# BT832A.net
KiCad netlist of a schematic drawn in EAGLE
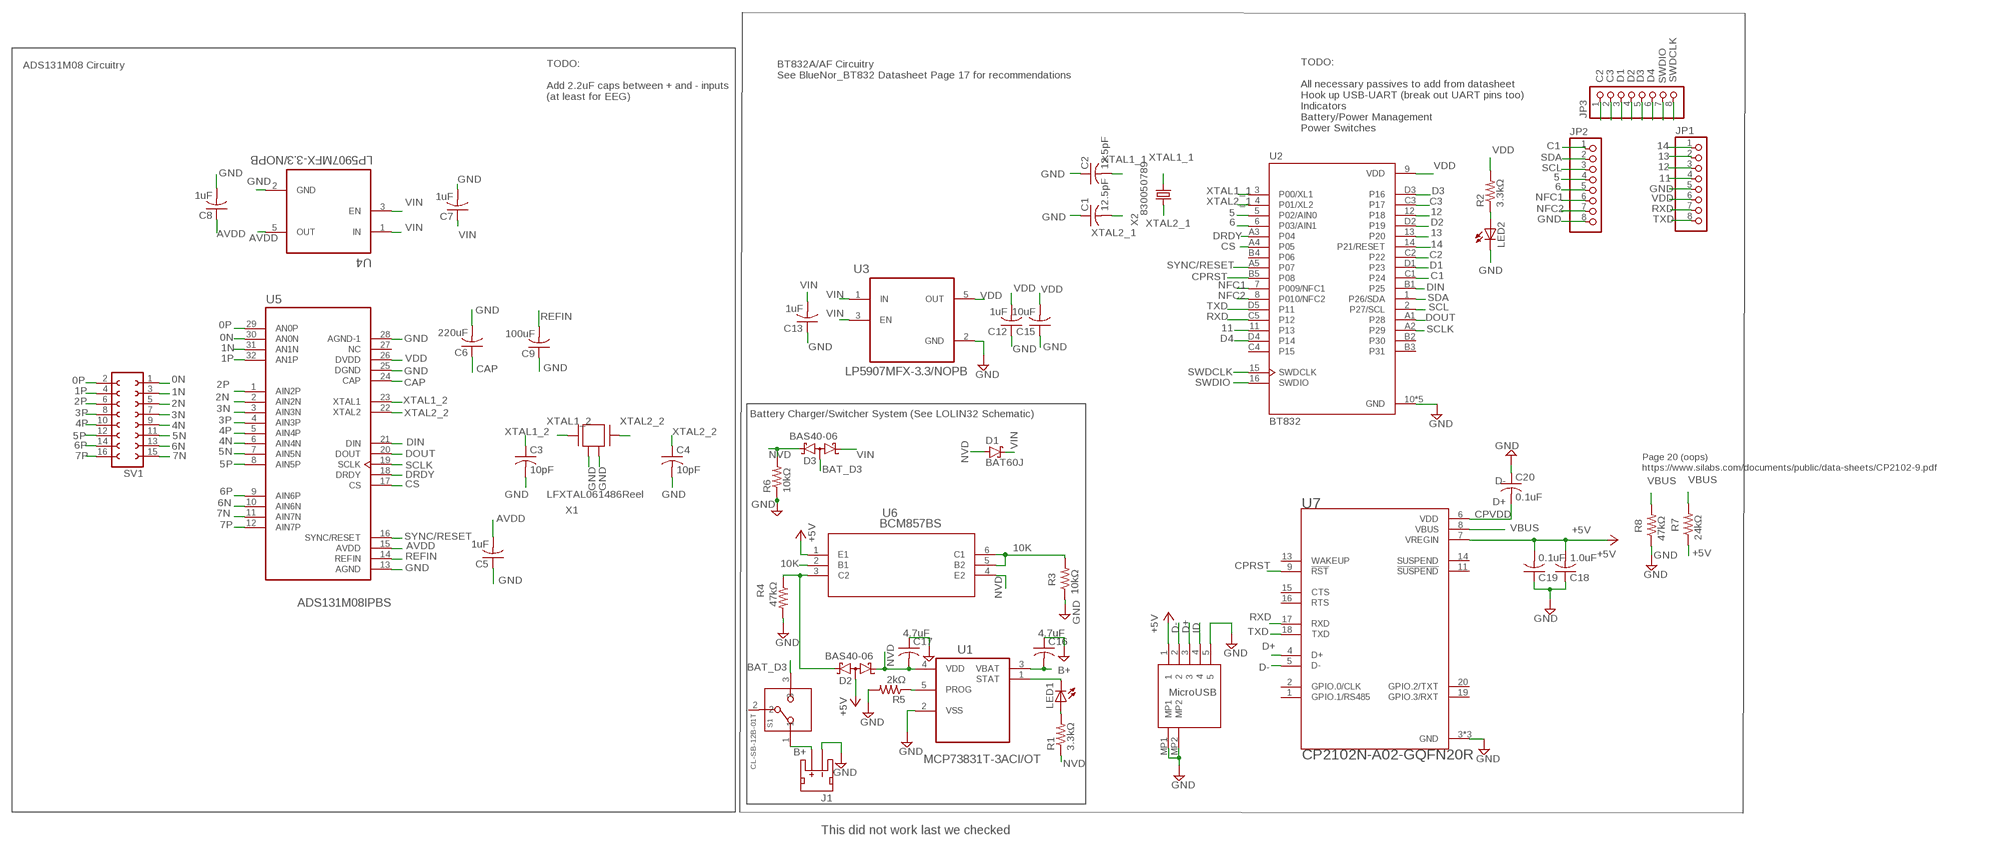
[diagram p0: schematic, sheet 1]

(export (version "E")
  (design (tool "Eeschema 10.0.6"))
  (components
    (comp (ref "C1")
      (value "12.5pF")
      (footprint "eagle-import:C0402")
      (libsource (lib "eagle-import") (part "adafruit_420_C-USC0402"))
    )
    (comp (ref "C2")
      (value "12.5pF")
      (footprint "eagle-import:C0402")
      (libsource (lib "eagle-import") (part "adafruit_420_C-USC0402"))
    )
    (comp (ref "C3")
      (value "10pF")
      (footprint "eagle-import:C0402")
      (libsource (lib "eagle-import") (part "adafruit_420_C-USC0402"))
    )
    (comp (ref "C4")
      (value "10pF")
      (footprint "eagle-import:C0402")
      (libsource (lib "eagle-import") (part "adafruit_420_C-USC0402"))
    )
    (comp (ref "C5")
      (value "1uF")
      (footprint "eagle-import:C0402")
      (libsource (lib "eagle-import") (part "C-USC0402"))
    )
    (comp (ref "C6")
      (value "220uF")
      (footprint "eagle-import:C0402")
      (libsource (lib "eagle-import") (part "C-USC0402"))
    )
    (comp (ref "C7")
      (value "1uF")
      (footprint "eagle-import:C0402")
      (libsource (lib "eagle-import") (part "C-USC0402"))
    )
    (comp (ref "C8")
      (value "1uF")
      (footprint "eagle-import:C0402")
      (libsource (lib "eagle-import") (part "C-USC0402"))
    )
    (comp (ref "C9")
      (value "100uF")
      (footprint "eagle-import:C0402")
      (libsource (lib "eagle-import") (part "C-USC0402"))
    )
    (comp (ref "C12")
      (value "1uF")
      (footprint "eagle-import:C0402")
      (libsource (lib "eagle-import") (part "C-USC0402"))
    )
    (comp (ref "C13")
      (value "1uF")
      (footprint "eagle-import:C0402")
      (libsource (lib "eagle-import") (part "C-USC0402"))
    )
    (comp (ref "C15")
      (value "10uF")
      (footprint "eagle-import:C0402")
      (libsource (lib "eagle-import") (part "C-USC0402"))
    )
    (comp (ref "C16")
      (value "4.7uF")
      (footprint "eagle-import:C0402")
      (libsource (lib "eagle-import") (part "adafruit_420_C-USC0402"))
    )
    (comp (ref "C17")
      (value "4.7uF")
      (footprint "eagle-import:C0402")
      (libsource (lib "eagle-import") (part "adafruit_420_C-USC0402"))
    )
    (comp (ref "C18")
      (value "1.0uF")
      (footprint "eagle-import:C0402")
      (libsource (lib "eagle-import") (part "adafruit_420_C-USC0402"))
    )
    (comp (ref "C19")
      (value "0.1uF")
      (footprint "eagle-import:C0402")
      (libsource (lib "eagle-import") (part "adafruit_420_C-USC0402"))
    )
    (comp (ref "C20")
      (value "0.1uF")
      (footprint "eagle-import:C0402")
      (libsource (lib "eagle-import") (part "adafruit_420_C-USC0402"))
    )
    (comp (ref "D1")
      (value "BAT60J")
      (footprint "eagle-import:SOD323_ST")
      (libsource (lib "eagle-import") (part "BAT60J"))
    )
    (comp (ref "D2")
      (value "BAS40-06")
      (footprint "eagle-import:SOT23")
      (libsource (lib "eagle-import") (part "BAS40-06"))
    )
    (comp (ref "D3")
      (value "BAS40-06")
      (footprint "eagle-import:SOT23")
      (libsource (lib "eagle-import") (part "BAS40-06"))
    )
    (comp (ref "J1")
      (value "JST_2MM_MALE")
      (footprint "eagle-import:JST-2-SMD")
      (libsource (lib "eagle-import") (part "JST_2MM_MALE"))
    )
    (comp (ref "JP1")
      (value "PINHD-1X8CLEANBIG")
      (footprint "eagle-import:1X08-CLEANBIG")
      (libsource (lib "eagle-import") (part "PINHD-1X8CLEANBIG"))
    )
    (comp (ref "JP2")
      (value "PINHD-1X8CLEANBIG")
      (footprint "eagle-import:1X08-CLEANBIG")
      (libsource (lib "eagle-import") (part "PINHD-1X8CLEANBIG"))
    )
    (comp (ref "JP3")
      (value "PINHD-1X8CLEANBIG")
      (footprint "eagle-import:1X08-CLEANBIG")
      (libsource (lib "eagle-import") (part "PINHD-1X8CLEANBIG"))
    )
    (comp (ref "LED1")
      (value "LEDCHIP-LED0603")
      (footprint "eagle-import:CHIP-LED0603")
      (libsource (lib "eagle-import") (part "LEDCHIP-LED0603"))
    )
    (comp (ref "LED2")
      (value "LEDCHIP-LED0603")
      (footprint "eagle-import:CHIP-LED0603")
      (libsource (lib "eagle-import") (part "LEDCHIP-LED0603"))
    )
    (comp (ref "R1")
      (value "3.3kΩ")
      (footprint "eagle-import:R0402")
      (libsource (lib "eagle-import") (part "R-US_R0402"))
    )
    (comp (ref "R2")
      (value "3.3kΩ")
      (footprint "eagle-import:R0402")
      (libsource (lib "eagle-import") (part "R-US_R0402"))
    )
    (comp (ref "R3")
      (value "10kΩ")
      (footprint "eagle-import:R0402")
      (libsource (lib "eagle-import") (part "R-US_R0402"))
    )
    (comp (ref "R4")
      (value "47kΩ")
      (footprint "eagle-import:R0402")
      (libsource (lib "eagle-import") (part "R-US_R0402"))
    )
    (comp (ref "R5")
      (value "2kΩ")
      (footprint "eagle-import:R0402")
      (libsource (lib "eagle-import") (part "R-US_R0402"))
    )
    (comp (ref "R6")
      (value "10kΩ")
      (footprint "eagle-import:R0402")
      (libsource (lib "eagle-import") (part "R-US_R0402"))
    )
    (comp (ref "R7")
      (value "24kΩ")
      (footprint "eagle-import:R0402")
      (libsource (lib "eagle-import") (part "R-US_R0402"))
    )
    (comp (ref "R8")
      (value "47kΩ")
      (footprint "eagle-import:R0402")
      (libsource (lib "eagle-import") (part "R-US_R0402"))
    )
    (comp (ref "S1")
      (value "CL-SB-12B-01T")
      (footprint "eagle-import:CL-SB-12B")
      (fields (field (name "MF") "Nidec Copal"))
      (libsource (lib "eagle-import") (part "CL-SB-12B-01T"))
    )
    (comp (ref "SV1")
      (value "FE08-2")
      (footprint "eagle-import:FE08-2")
      (libsource (lib "eagle-import") (part "FE08-2"))
    )
    (comp (ref "U$1")
      (value "DX4R005JJ2R1800")
      (footprint "eagle-import:DX4R005JJ2R1800")
      (fields (field (name "MF") "JAE Electronics"))
      (libsource (lib "eagle-import") (part "DX4R005JJ2R1800"))
    )
    (comp (ref "U1")
      (value "MCP73831T-3ACI/OT")
      (footprint "eagle-import:SOT95P270X145-5N")
      (fields (field (name "MF") "Microchip"))
      (libsource (lib "eagle-import") (part "MCP73831T-3ACI/OT"))
    )
    (comp (ref "U2")
      (value "BT832")
      (footprint "eagle-import:BLEMODULE_BT832")
      (fields (field (name "MF") "Fanstel Corp."))
      (libsource (lib "eagle-import") (part "BT832"))
    )
    (comp (ref "U3")
      (value "LP5907MFX-3.3/NOPB")
      (footprint "eagle-import:SOT95P280X145-5N")
      (fields (field (name "MF") "Texas Instruments"))
      (libsource (lib "eagle-import") (part "LP5907MFX-3.3/NOPB"))
    )
    (comp (ref "U4")
      (value "LP5907MFX-3.3/NOPB")
      (footprint "eagle-import:SOT95P280X145-5N")
      (fields (field (name "MF") "Texas Instruments"))
      (libsource (lib "eagle-import") (part "LP5907MFX-3.3/NOPB"))
    )
    (comp (ref "U5")
      (value "ADS131M08IPBS")
      (footprint "eagle-import:QFP50P700X700X120-32N")
      (fields (field (name "MF") "Texas Instruments"))
      (libsource (lib "eagle-import") (part "ADS131M08IPBS"))
    )
    (comp (ref "U6")
      (value "BCM857BS")
      (footprint "eagle-import:SOT363_NEX")
      (fields (field (name "COPYRIGHT") "Copyright (C) 2016 Accelerated Designs. All rights reserved"))
      (libsource (lib "eagle-import") (part "BCM857BS"))
    )
    (comp (ref "U7")
      (value "CP2102N-A02-GQFN20R")
      (footprint "eagle-import:SILABS_CP2102N-A02-GQFN20R")
      (fields (field (name "MF") "Silicon Labs"))
      (libsource (lib "eagle-import") (part "CP2102N-A02-GQFN20R"))
    )
    (comp (ref "X1")
      (value "ABM3B-8.000MHZ-B2-T")
      (footprint "eagle-import:ABM3B-8.000MHZ-B2-T")
      (fields
        (field (name "DIGIKEY_PART_NUMBER") "535-9720-2-ND")
        (field (name "MANUFACTURER") "Abracon LLC")
        (field (name "CREATED_BY") "PCBLayout.com")
      )
      (libsource (lib "eagle-import") (part "ABM3B-8.000MHZ-B2-T"))
    )
    (comp (ref "X2")
      (value "FC-12M")
      (footprint "eagle-import:FC-12M")
      (libsource (lib "eagle-import") (part "FC-12M"))
    )
  )
  (nets
    (net (code "1") (name "+5V") (class "Default")
      (node (ref "C18") (pin "2") (pinfunction "2_2") (pintype "passive"))
      (node (ref "C19") (pin "2") (pinfunction "2_2") (pintype "passive"))
      (node (ref "D2") (pin "3") (pinfunction "AA_3") (pintype "passive"))
      (node (ref "R7") (pin "1") (pinfunction "1_1") (pintype "passive"))
      (node (ref "U$1") (pin "1") (pinfunction "1_1") (pintype "bidirectional"))
      (node (ref "U6") (pin "1") (pinfunction "E1_1") (pintype "passive"))
      (node (ref "U7") (pin "7") (pinfunction "VREGIN_7") (pintype "power_in"))
    )
    (net (code "2") (name "0N") (class "Default")
      (node (ref "SV1") (pin "1") (pinfunction "1_1") (pintype "passive"))
      (node (ref "U5") (pin "30") (pinfunction "AN0N_30") (pintype "bidirectional"))
    )
    (net (code "3") (name "0P") (class "Default")
      (node (ref "SV1") (pin "2") (pinfunction "2_2") (pintype "passive"))
      (node (ref "U5") (pin "29") (pinfunction "AN0P_29") (pintype "bidirectional"))
    )
    (net (code "4") (name "1N") (class "Default")
      (node (ref "SV1") (pin "3") (pinfunction "3_3") (pintype "passive"))
      (node (ref "U5") (pin "31") (pinfunction "AN1N_31") (pintype "bidirectional"))
    )
    (net (code "5") (name "1P") (class "Default")
      (node (ref "SV1") (pin "4") (pinfunction "4_4") (pintype "passive"))
      (node (ref "U5") (pin "32") (pinfunction "AN1P_32") (pintype "bidirectional"))
    )
    (net (code "6") (name "2N") (class "Default")
      (node (ref "SV1") (pin "5") (pinfunction "5_5") (pintype "passive"))
      (node (ref "U5") (pin "2") (pinfunction "AIN2N_2") (pintype "input"))
    )
    (net (code "7") (name "2P") (class "Default")
      (node (ref "SV1") (pin "6") (pinfunction "6_6") (pintype "passive"))
      (node (ref "U5") (pin "1") (pinfunction "AIN2P_1") (pintype "input"))
    )
    (net (code "8") (name "3N") (class "Default")
      (node (ref "SV1") (pin "7") (pinfunction "7_7") (pintype "passive"))
      (node (ref "U5") (pin "3") (pinfunction "AIN3N_3") (pintype "input"))
    )
    (net (code "9") (name "3P") (class "Default")
      (node (ref "SV1") (pin "8") (pinfunction "8_8") (pintype "passive"))
      (node (ref "U5") (pin "4") (pinfunction "AIN3P_4") (pintype "input"))
    )
    (net (code "10") (name "4N") (class "Default")
      (node (ref "SV1") (pin "9") (pinfunction "9_9") (pintype "passive"))
      (node (ref "U5") (pin "6") (pinfunction "AIN4N_6") (pintype "input"))
    )
    (net (code "11") (name "4P") (class "Default")
      (node (ref "SV1") (pin "10") (pinfunction "10_10") (pintype "passive"))
      (node (ref "U5") (pin "5") (pinfunction "AIN4P_5") (pintype "input"))
    )
    (net (code "12") (name "5") (class "Default")
      (node (ref "JP2") (pin "4") (pinfunction "4_4") (pintype "passive"))
      (node (ref "U2") (pin "5") (pinfunction "P02/AIN0_5") (pintype "bidirectional"))
    )
    (net (code "13") (name "5N") (class "Default")
      (node (ref "SV1") (pin "11") (pinfunction "11_11") (pintype "passive"))
      (node (ref "U5") (pin "7") (pinfunction "AIN5N_7") (pintype "input"))
    )
    (net (code "14") (name "5P") (class "Default")
      (node (ref "SV1") (pin "12") (pinfunction "12_12") (pintype "passive"))
      (node (ref "U5") (pin "8") (pinfunction "AIN5P_8") (pintype "input"))
    )
    (net (code "15") (name "6") (class "Default")
      (node (ref "JP2") (pin "5") (pinfunction "5_5") (pintype "passive"))
      (node (ref "U2") (pin "6") (pinfunction "P03/AIN1_6") (pintype "bidirectional"))
    )
    (net (code "16") (name "6N") (class "Default")
      (node (ref "SV1") (pin "13") (pinfunction "13_13") (pintype "passive"))
      (node (ref "U5") (pin "10") (pinfunction "AIN6N_10") (pintype "input"))
    )
    (net (code "17") (name "6P") (class "Default")
      (node (ref "SV1") (pin "14") (pinfunction "14_14") (pintype "passive"))
      (node (ref "U5") (pin "9") (pinfunction "AIN6P_9") (pintype "input"))
    )
    (net (code "18") (name "7N") (class "Default")
      (node (ref "SV1") (pin "15") (pinfunction "15_15") (pintype "passive"))
      (node (ref "U5") (pin "11") (pinfunction "AIN7N_11") (pintype "input"))
    )
    (net (code "19") (name "7P") (class "Default")
      (node (ref "SV1") (pin "16") (pinfunction "16_16") (pintype "passive"))
      (node (ref "U5") (pin "12") (pinfunction "AIN7P_12") (pintype "input"))
    )
    (net (code "20") (name "10K") (class "Default")
      (node (ref "R3") (pin "2") (pinfunction "2_2") (pintype "passive"))
      (node (ref "U6") (pin "2") (pinfunction "B1_2") (pintype "passive"))
      (node (ref "U6") (pin "5") (pinfunction "B2_5") (pintype "passive"))
      (node (ref "U6") (pin "6") (pinfunction "C1_6") (pintype "passive"))
    )
    (net (code "21") (name "11") (class "Default")
      (node (ref "JP1") (pin "4") (pinfunction "4_4") (pintype "passive"))
      (node (ref "U2") (pin "11") (pinfunction "P13_11") (pintype "bidirectional"))
    )
    (net (code "22") (name "12") (class "Default")
      (node (ref "JP1") (pin "3") (pinfunction "3_3") (pintype "passive"))
      (node (ref "U2") (pin "12") (pinfunction "P18_12") (pintype "bidirectional"))
    )
    (net (code "23") (name "13") (class "Default")
      (node (ref "JP1") (pin "2") (pinfunction "2_2") (pintype "passive"))
      (node (ref "U2") (pin "13") (pinfunction "P20_13") (pintype "bidirectional"))
    )
    (net (code "24") (name "14") (class "Default")
      (node (ref "JP1") (pin "1") (pinfunction "1_1") (pintype "passive"))
      (node (ref "U2") (pin "14") (pinfunction "P21/RESET_14") (pintype "bidirectional"))
    )
    (net (code "25") (name "AVDD") (class "Default")
      (node (ref "C5") (pin "2") (pinfunction "2_2") (pintype "passive"))
      (node (ref "C8") (pin "1") (pinfunction "1_1") (pintype "passive"))
      (node (ref "U4") (pin "5") (pinfunction "OUT_5") (pintype "output"))
      (node (ref "U5") (pin "15") (pinfunction "AVDD_15") (pintype "power_in"))
    )
    (net (code "26") (name "B+") (class "Default")
      (node (ref "C16") (pin "2") (pinfunction "2_2") (pintype "passive"))
      (node (ref "J1") (pin "2") (pinfunction "+_2") (pintype "bidirectional"))
      (node (ref "S1") (pin "1") (pinfunction "1_1") (pintype "bidirectional"))
      (node (ref "U1") (pin "3") (pinfunction "VBAT_3") (pintype "power_in"))
    )
    (net (code "27") (name "BAT_D3") (class "Default")
      (node (ref "D3") (pin "3") (pinfunction "AA_3") (pintype "passive"))
      (node (ref "S1") (pin "3") (pinfunction "3_3") (pintype "bidirectional"))
    )
    (net (code "28") (name "C1") (class "Default")
      (node (ref "JP2") (pin "1") (pinfunction "1_1") (pintype "passive"))
      (node (ref "U2") (pin "C1") (pinfunction "P24_C1") (pintype "bidirectional"))
    )
    (net (code "29") (name "C2") (class "Default")
      (node (ref "JP3") (pin "1") (pinfunction "1_1") (pintype "passive"))
      (node (ref "U2") (pin "C2") (pinfunction "P22_C2") (pintype "bidirectional"))
    )
    (net (code "30") (name "C3") (class "Default")
      (node (ref "JP3") (pin "2") (pinfunction "2_2") (pintype "passive"))
      (node (ref "U2") (pin "C3") (pinfunction "P17_C3") (pintype "bidirectional"))
    )
    (net (code "31") (name "CAP") (class "Default")
      (node (ref "C6") (pin "1") (pinfunction "1_1") (pintype "passive"))
      (node (ref "U5") (pin "24") (pinfunction "CAP_24") (pintype "bidirectional"))
    )
    (net (code "32") (name "CPRST") (class "Default")
      (node (ref "U2") (pin "B5") (pinfunction "P08_B5") (pintype "bidirectional"))
      (node (ref "U7") (pin "9") (pinfunction "~{RST}_9") (pintype "input"))
    )
    (net (code "33") (name "CPVDD") (class "Default")
      (node (ref "C20") (pin "2") (pinfunction "2_2") (pintype "passive"))
      (node (ref "U7") (pin "6") (pinfunction "VDD_6") (pintype "power_in"))
    )
    (net (code "34") (name "CS") (class "Default")
      (node (ref "U2") (pin "A4") (pinfunction "P05_A4") (pintype "bidirectional"))
      (node (ref "U5") (pin "17") (pinfunction "CS_17") (pintype "bidirectional"))
    )
    (net (code "35") (name "D+") (class "Default")
      (node (ref "U$1") (pin "3") (pinfunction "3_3") (pintype "bidirectional"))
      (node (ref "U7") (pin "4") (pinfunction "D+_4") (pintype "bidirectional"))
    )
    (net (code "36") (name "D-") (class "Default")
      (node (ref "U$1") (pin "2") (pinfunction "2_2") (pintype "bidirectional"))
      (node (ref "U7") (pin "5") (pinfunction "D-_5") (pintype "bidirectional"))
    )
    (net (code "37") (name "D1") (class "Default")
      (node (ref "JP3") (pin "3") (pinfunction "3_3") (pintype "passive"))
      (node (ref "U2") (pin "D1") (pinfunction "P23_D1") (pintype "bidirectional"))
    )
    (net (code "38") (name "D2") (class "Default")
      (node (ref "JP3") (pin "4") (pinfunction "4_4") (pintype "passive"))
      (node (ref "U2") (pin "D2") (pinfunction "P19_D2") (pintype "bidirectional"))
    )
    (net (code "39") (name "D3") (class "Default")
      (node (ref "JP3") (pin "5") (pinfunction "5_5") (pintype "passive"))
      (node (ref "U2") (pin "D3") (pinfunction "P16_D3") (pintype "bidirectional"))
    )
    (net (code "40") (name "D4") (class "Default")
      (node (ref "JP3") (pin "6") (pinfunction "6_6") (pintype "passive"))
      (node (ref "U2") (pin "D4") (pinfunction "P14_D4") (pintype "bidirectional"))
    )
    (net (code "41") (name "DIN") (class "Default")
      (node (ref "U2") (pin "B1") (pinfunction "P25_B1") (pintype "bidirectional"))
      (node (ref "U5") (pin "21") (pinfunction "DIN_21") (pintype "input"))
    )
    (net (code "42") (name "DOUT") (class "Default")
      (node (ref "U2") (pin "A1") (pinfunction "P28_A1") (pintype "bidirectional"))
      (node (ref "U5") (pin "20") (pinfunction "DOUT_20") (pintype "output"))
    )
    (net (code "43") (name "DRDY") (class "Default")
      (node (ref "U2") (pin "A3") (pinfunction "P04_A3") (pintype "bidirectional"))
      (node (ref "U5") (pin "18") (pinfunction "DRDY_18") (pintype "output"))
    )
    (net (code "44") (name "GND") (class "Default")
      (node (ref "C1") (pin "1") (pinfunction "1_1") (pintype "passive"))
      (node (ref "C12") (pin "1") (pinfunction "1_1") (pintype "passive"))
      (node (ref "C13") (pin "1") (pinfunction "1_1") (pintype "passive"))
      (node (ref "C15") (pin "1") (pinfunction "1_1") (pintype "passive"))
      (node (ref "C16") (pin "1") (pinfunction "1_1") (pintype "passive"))
      (node (ref "C17") (pin "1") (pinfunction "1_1") (pintype "passive"))
      (node (ref "C18") (pin "1") (pinfunction "1_1") (pintype "passive"))
      (node (ref "C19") (pin "1") (pinfunction "1_1") (pintype "passive"))
      (node (ref "C2") (pin "1") (pinfunction "1_1") (pintype "passive"))
      (node (ref "C20") (pin "1") (pinfunction "1_1") (pintype "passive"))
      (node (ref "C3") (pin "2") (pinfunction "2_2") (pintype "passive"))
      (node (ref "C4") (pin "2") (pinfunction "2_2") (pintype "passive"))
      (node (ref "C5") (pin "1") (pinfunction "1_1") (pintype "passive"))
      (node (ref "C6") (pin "2") (pinfunction "2_2") (pintype "passive"))
      (node (ref "C7") (pin "2") (pinfunction "2_2") (pintype "passive"))
      (node (ref "C8") (pin "2") (pinfunction "2_2") (pintype "passive"))
      (node (ref "C9") (pin "1") (pinfunction "1_1") (pintype "passive"))
      (node (ref "J1") (pin "1") (pinfunction "-_1") (pintype "bidirectional"))
      (node (ref "JP1") (pin "5") (pinfunction "5_5") (pintype "passive"))
      (node (ref "JP2") (pin "8") (pinfunction "8_8") (pintype "passive"))
      (node (ref "LED2") (pin "C") (pinfunction "C_C") (pintype "passive"))
      (node (ref "R3") (pin "1") (pinfunction "1_1") (pintype "passive"))
      (node (ref "R4") (pin "2") (pinfunction "2_2") (pintype "passive"))
      (node (ref "R5") (pin "2") (pinfunction "2_2") (pintype "passive"))
      (node (ref "R6") (pin "1") (pinfunction "1_1") (pintype "passive"))
      (node (ref "R8") (pin "1") (pinfunction "1_1") (pintype "passive"))
      (node (ref "U$1") (pin "5") (pinfunction "5_5") (pintype "bidirectional"))
      (node (ref "U$1") (pin "MP1") (pinfunction "MP1_MP1") (pintype "bidirectional"))
      (node (ref "U$1") (pin "MP2") (pinfunction "MP2_MP2") (pintype "bidirectional"))
      (node (ref "U1") (pin "2") (pinfunction "VSS_2") (pintype "power_in"))
      (node (ref "U2") (pin "10") (pinfunction "GND_10") (pintype "power_in"))
      (node (ref "U2") (pin "A0") (pinfunction "GND_A0") (pintype "power_in"))
      (node (ref "U2") (pin "B0") (pinfunction "GND_B0") (pintype "power_in"))
      (node (ref "U2") (pin "C0") (pinfunction "GND_C0") (pintype "power_in"))
      (node (ref "U2") (pin "D0") (pinfunction "GND_D0") (pintype "power_in"))
      (node (ref "U3") (pin "2") (pinfunction "GND_2") (pintype "power_in"))
      (node (ref "U4") (pin "2") (pinfunction "GND_2") (pintype "power_in"))
      (node (ref "U5") (pin "13") (pinfunction "AGND_13") (pintype "power_in"))
      (node (ref "U5") (pin "25") (pinfunction "DGND_25") (pintype "power_in"))
      (node (ref "U5") (pin "28") (pinfunction "AGND-1_28") (pintype "power_in"))
      (node (ref "U7") (pin "12") (pinfunction "GND_12") (pintype "power_in"))
      (node (ref "U7") (pin "21") (pinfunction "GND_21") (pintype "power_in"))
      (node (ref "U7") (pin "3") (pinfunction "GND_3") (pintype "power_in"))
      (node (ref "X1") (pin "2") (pinfunction "2_2") (pintype "passive"))
      (node (ref "X1") (pin "4") (pinfunction "4_4") (pintype "passive"))
    )
    (net (code "45") (name "ID") (class "Default")
      (node (ref "U$1") (pin "4") (pinfunction "4_4") (pintype "bidirectional"))
    )
    (net (code "46") (name "NFC1") (class "Default")
      (node (ref "JP2") (pin "6") (pinfunction "6_6") (pintype "passive"))
      (node (ref "U2") (pin "7") (pinfunction "P009/NFC1_7") (pintype "bidirectional"))
    )
    (net (code "47") (name "NFC2") (class "Default")
      (node (ref "JP2") (pin "7") (pinfunction "7_7") (pintype "passive"))
      (node (ref "U2") (pin "8") (pinfunction "P010/NFC2_8") (pintype "bidirectional"))
    )
    (net (code "48") (name "NVD") (class "Default")
      (node (ref "C17") (pin "2") (pinfunction "2_2") (pintype "passive"))
      (node (ref "D1") (pin "A") (pinfunction "A_A") (pintype "passive"))
      (node (ref "D2") (pin "1") (pinfunction "K1_1") (pintype "passive"))
      (node (ref "D3") (pin "2") (pinfunction "K2_2") (pintype "passive"))
      (node (ref "R1") (pin "1") (pinfunction "1_1") (pintype "passive"))
      (node (ref "R6") (pin "2") (pinfunction "2_2") (pintype "passive"))
      (node (ref "U1") (pin "4") (pinfunction "VDD_4") (pintype "power_in"))
      (node (ref "U6") (pin "4") (pinfunction "E2_4") (pintype "passive"))
    )
    (net (code "49") (name "Net-(D2-K2)") (class "Default")
      (node (ref "D2") (pin "2") (pinfunction "K2_2") (pintype "passive"))
      (node (ref "R4") (pin "1") (pinfunction "1_1") (pintype "passive"))
      (node (ref "U6") (pin "3") (pinfunction "C2_3") (pintype "passive"))
    )
    (net (code "50") (name "Net-(LED1-PadA)") (class "Default")
      (node (ref "LED1") (pin "A") (pinfunction "A_A") (pintype "passive"))
      (node (ref "R1") (pin "2") (pinfunction "2_2") (pintype "passive"))
    )
    (net (code "51") (name "Net-(LED2-PadA)") (class "Default")
      (node (ref "LED2") (pin "A") (pinfunction "A_A") (pintype "passive"))
      (node (ref "R2") (pin "1") (pinfunction "1_1") (pintype "passive"))
    )
    (net (code "52") (name "Net-(U1-PROG)") (class "Default")
      (node (ref "R5") (pin "1") (pinfunction "1_1") (pintype "passive"))
      (node (ref "U1") (pin "5") (pinfunction "PROG_5") (pintype "input"))
    )
    (net (code "53") (name "Net-(U1-STAT)") (class "Default")
      (node (ref "LED1") (pin "C") (pinfunction "C_C") (pintype "passive"))
      (node (ref "U1") (pin "1") (pinfunction "STAT_1") (pintype "output"))
    )
    (net (code "54") (name "REFIN") (class "Default")
      (node (ref "C9") (pin "2") (pinfunction "2_2") (pintype "passive"))
      (node (ref "U5") (pin "14") (pinfunction "REFIN_14") (pintype "input"))
    )
    (net (code "55") (name "RXD") (class "Default")
      (node (ref "JP1") (pin "7") (pinfunction "7_7") (pintype "passive"))
      (node (ref "U2") (pin "C5") (pinfunction "P12_C5") (pintype "bidirectional"))
      (node (ref "U7") (pin "17") (pinfunction "RXD_17") (pintype "input"))
    )
    (net (code "56") (name "SCL") (class "Default")
      (node (ref "JP2") (pin "3") (pinfunction "3_3") (pintype "passive"))
      (node (ref "U2") (pin "2") (pinfunction "P27/SCL_2") (pintype "bidirectional"))
    )
    (net (code "57") (name "SCLK") (class "Default")
      (node (ref "U2") (pin "A2") (pinfunction "P29_A2") (pintype "bidirectional"))
      (node (ref "U5") (pin "19") (pinfunction "SCLK_19") (pintype "input"))
    )
    (net (code "58") (name "SDA") (class "Default")
      (node (ref "JP2") (pin "2") (pinfunction "2_2") (pintype "passive"))
      (node (ref "U2") (pin "1") (pinfunction "P26/SDA_1") (pintype "bidirectional"))
    )
    (net (code "59") (name "SWDCLK") (class "Default")
      (node (ref "JP3") (pin "8") (pinfunction "8_8") (pintype "passive"))
      (node (ref "U2") (pin "15") (pinfunction "SWDCLK_15") (pintype "input"))
    )
    (net (code "60") (name "SWDIO") (class "Default")
      (node (ref "JP3") (pin "7") (pinfunction "7_7") (pintype "passive"))
      (node (ref "U2") (pin "16") (pinfunction "SWDIO_16") (pintype "bidirectional"))
    )
    (net (code "61") (name "SYNC{slash}RESET") (class "Default")
      (node (ref "U2") (pin "A5") (pinfunction "P07_A5") (pintype "bidirectional"))
      (node (ref "U5") (pin "16") (pinfunction "SYNC/RESET_16") (pintype "bidirectional"))
    )
    (net (code "62") (name "TXD") (class "Default")
      (node (ref "JP1") (pin "8") (pinfunction "8_8") (pintype "passive"))
      (node (ref "U2") (pin "D5") (pinfunction "P11_D5") (pintype "bidirectional"))
      (node (ref "U7") (pin "18") (pinfunction "TXD_18") (pintype "output"))
    )
    (net (code "63") (name "VBUS") (class "Default")
      (node (ref "R7") (pin "2") (pinfunction "2_2") (pintype "passive"))
      (node (ref "R8") (pin "2") (pinfunction "2_2") (pintype "passive"))
      (node (ref "U7") (pin "8") (pinfunction "VBUS_8") (pintype "power_in"))
    )
    (net (code "64") (name "VDD") (class "Default")
      (node (ref "C12") (pin "2") (pinfunction "2_2") (pintype "passive"))
      (node (ref "C15") (pin "2") (pinfunction "2_2") (pintype "passive"))
      (node (ref "JP1") (pin "6") (pinfunction "6_6") (pintype "passive"))
      (node (ref "R2") (pin "2") (pinfunction "2_2") (pintype "passive"))
      (node (ref "U2") (pin "9") (pinfunction "VDD_9") (pintype "power_in"))
      (node (ref "U3") (pin "5") (pinfunction "OUT_5") (pintype "output"))
      (node (ref "U5") (pin "26") (pinfunction "DVDD_26") (pintype "power_in"))
    )
    (net (code "65") (name "VIN") (class "Default")
      (node (ref "C13") (pin "2") (pinfunction "2_2") (pintype "passive"))
      (node (ref "C7") (pin "1") (pinfunction "1_1") (pintype "passive"))
      (node (ref "D1") (pin "C") (pinfunction "C_C") (pintype "passive"))
      (node (ref "D3") (pin "1") (pinfunction "K1_1") (pintype "passive"))
      (node (ref "U3") (pin "1") (pinfunction "IN_1") (pintype "input"))
      (node (ref "U3") (pin "3") (pinfunction "EN_3") (pintype "input"))
      (node (ref "U4") (pin "1") (pinfunction "IN_1") (pintype "input"))
      (node (ref "U4") (pin "3") (pinfunction "EN_3") (pintype "input"))
    )
    (net (code "66") (name "XTAL1_1") (class "Default")
      (node (ref "C2") (pin "2") (pinfunction "2_2") (pintype "passive"))
      (node (ref "U2") (pin "3") (pinfunction "P00/XL1_3") (pintype "bidirectional"))
      (node (ref "X2") (pin "2") (pinfunction "2_2") (pintype "passive"))
    )
    (net (code "67") (name "XTAL1_2") (class "Default")
      (node (ref "C3") (pin "1") (pinfunction "1_1") (pintype "passive"))
      (node (ref "U5") (pin "23") (pinfunction "XTAL1_23") (pintype "bidirectional"))
      (node (ref "X1") (pin "1") (pinfunction "1_1") (pintype "passive"))
    )
    (net (code "68") (name "XTAL2_1") (class "Default")
      (node (ref "C1") (pin "2") (pinfunction "2_2") (pintype "passive"))
      (node (ref "U2") (pin "4") (pinfunction "P01/XL2_4") (pintype "bidirectional"))
      (node (ref "X2") (pin "1") (pinfunction "1_1") (pintype "passive"))
    )
    (net (code "69") (name "XTAL2_2") (class "Default")
      (node (ref "C4") (pin "1") (pinfunction "1_1") (pintype "passive"))
      (node (ref "U5") (pin "22") (pinfunction "XTAL2_22") (pintype "bidirectional"))
      (node (ref "X1") (pin "3") (pinfunction "3_3") (pintype "passive"))
    )
    (net (code "70") (name "unconnected-(J1-PAD1-PadNC1)") (class "Default")
      (node (ref "J1") (pin "NC1") (pinfunction "PAD1_NC1") (pintype "bidirectional"))
    )
    (net (code "71") (name "unconnected-(J1-PAD2-PadNC2)") (class "Default")
      (node (ref "J1") (pin "NC2") (pinfunction "PAD2_NC2") (pintype "bidirectional"))
    )
    (net (code "72") (name "unconnected-(S1-Pad2)") (class "Default")
      (node (ref "S1") (pin "2") (pinfunction "2_2") (pintype "bidirectional"))
    )
    (net (code "73") (name "unconnected-(U2-P06-PadB4)") (class "Default")
      (node (ref "U2") (pin "B4") (pinfunction "P06_B4") (pintype "bidirectional"))
    )
    (net (code "74") (name "unconnected-(U2-P15-PadC4)") (class "Default")
      (node (ref "U2") (pin "C4") (pinfunction "P15_C4") (pintype "bidirectional"))
    )
    (net (code "75") (name "unconnected-(U2-P30-PadB2)") (class "Default")
      (node (ref "U2") (pin "B2") (pinfunction "P30_B2") (pintype "bidirectional"))
    )
    (net (code "76") (name "unconnected-(U2-P31-PadB3)") (class "Default")
      (node (ref "U2") (pin "B3") (pinfunction "P31_B3") (pintype "bidirectional"))
    )
    (net (code "77") (name "unconnected-(U5-NC-Pad27)") (class "Default")
      (node (ref "U5") (pin "27") (pinfunction "NC_27") (pintype "bidirectional"))
    )
    (net (code "78") (name "unconnected-(U7-CTS-Pad15)") (class "Default")
      (node (ref "U7") (pin "15") (pinfunction "CTS_15") (pintype "input"))
    )
    (net (code "79") (name "unconnected-(U7-GPIO.0{slash}CLK-Pad2)") (class "Default")
      (node (ref "U7") (pin "2") (pinfunction "GPIO.0/CLK_2") (pintype "bidirectional"))
    )
    (net (code "80") (name "unconnected-(U7-GPIO.1{slash}RS485-Pad1)") (class "Default")
      (node (ref "U7") (pin "1") (pinfunction "GPIO.1/RS485_1") (pintype "bidirectional"))
    )
    (net (code "81") (name "unconnected-(U7-GPIO.2{slash}TXT-Pad20)") (class "Default")
      (node (ref "U7") (pin "20") (pinfunction "GPIO.2/TXT_20") (pintype "bidirectional"))
    )
    (net (code "82") (name "unconnected-(U7-GPIO.3{slash}RXT-Pad19)") (class "Default")
      (node (ref "U7") (pin "19") (pinfunction "GPIO.3/RXT_19") (pintype "bidirectional"))
    )
    (net (code "83") (name "unconnected-(U7-RTS-Pad16)") (class "Default")
      (node (ref "U7") (pin "16") (pinfunction "RTS_16") (pintype "output"))
    )
    (net (code "84") (name "unconnected-(U7-SUSPEND-Pad14)") (class "Default")
      (node (ref "U7") (pin "14") (pinfunction "SUSPEND_14") (pintype "output"))
    )
    (net (code "85") (name "unconnected-(U7-WAKEUP-Pad13)") (class "Default")
      (node (ref "U7") (pin "13") (pinfunction "WAKEUP_13") (pintype "input"))
    )
    (net (code "86") (name "unconnected-(U7-~{SUSPEND}-Pad11)") (class "Default")
      (node (ref "U7") (pin "11") (pinfunction "~{SUSPEND}_11") (pintype "output"))
    )
  )
)
